# Sensing.net
KiCad netlist of a schematic drawn in Altium Designer
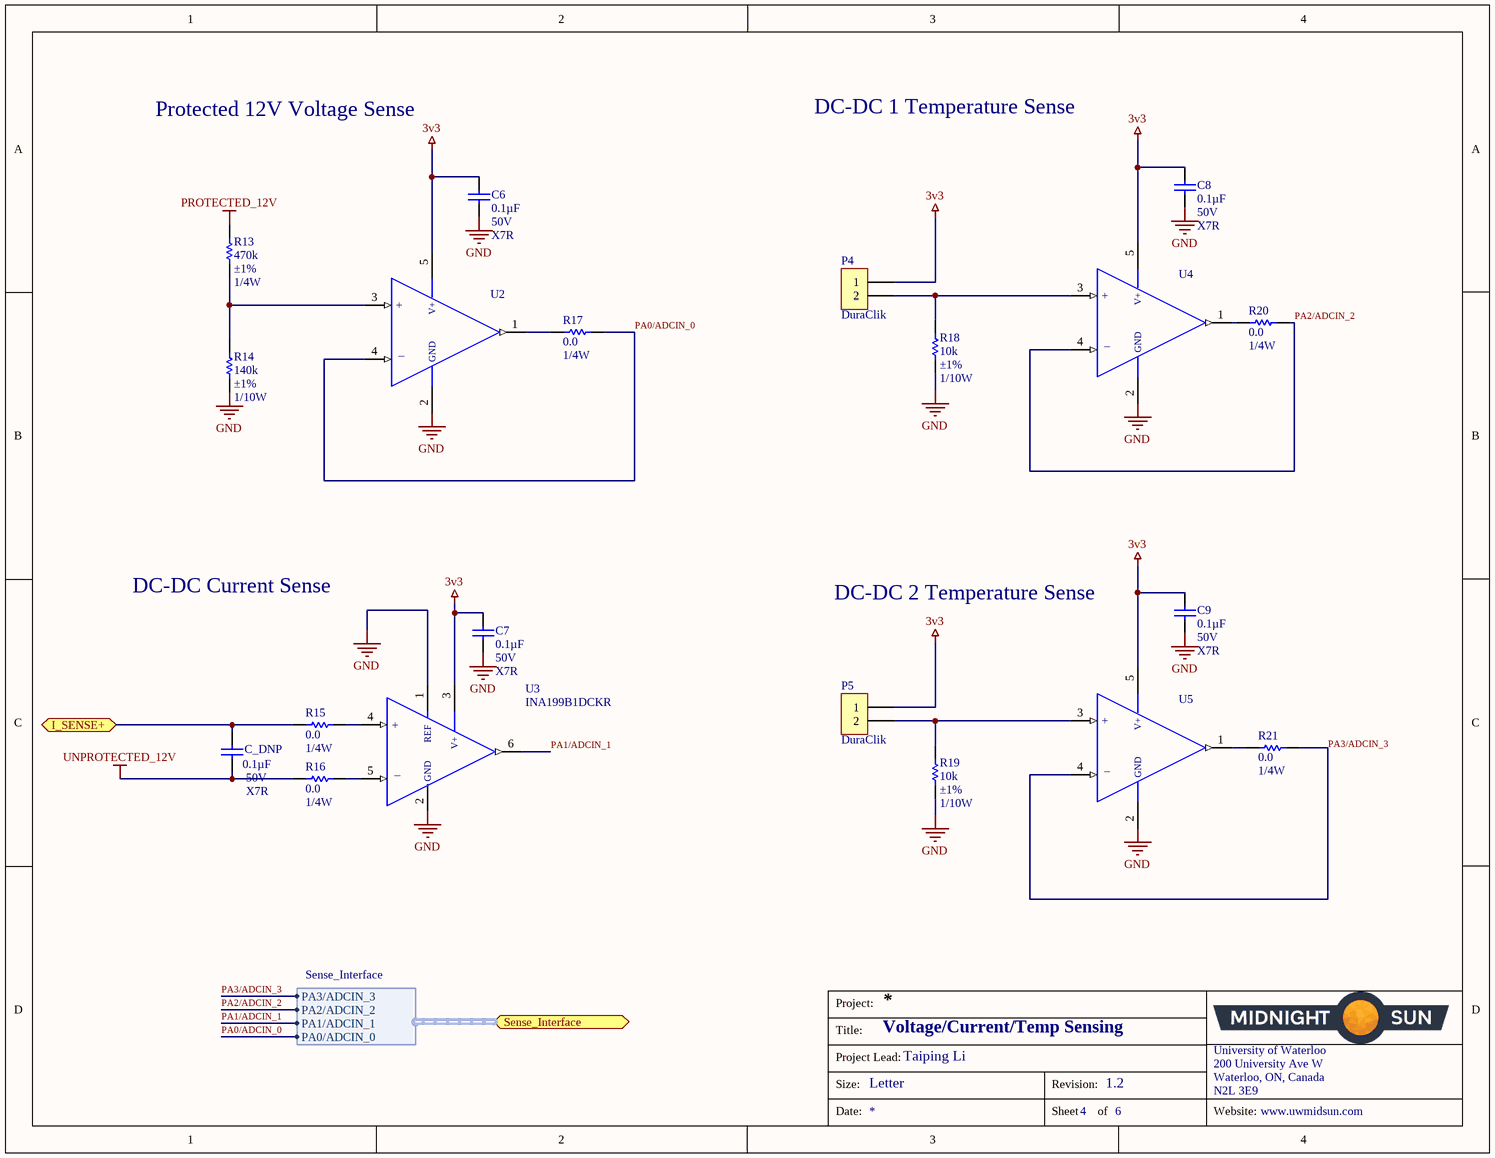
[diagram p0: Sensing.SchDoc]

(export (version "E")
  (design (tool "Eeschema 10.0.6"))
  (components
    (comp (ref "C6")
      (value "CAP CER 0.1UF 50V 10% X7R 0603")
      (footprint "CAP, 0603")
      (description "0.10µF ±10% 50V Ceramic Capacitor X7R 0603 (1608 Metric)")
      (fields
        (field (name "TOLERANCE") "±10%")
        (field (name "CAPACITANCE") "0.1µF")
        (field (name "VOLTAGE") "50V")
        (field (name "TEMPERATURE COEFFICIENT") "X7R")
      )
      (libsource (lib "Schematic Diagrams") (part "CAP CER 0.1UF 50V 10% X7R 0603"))
    )
    (comp (ref "C7")
      (value "CAP CER 0.1UF 50V 10% X7R 0603")
      (footprint "CAP, 0603")
      (description "0.10µF ±10% 50V Ceramic Capacitor X7R 0603 (1608 Metric)")
      (fields
        (field (name "TOLERANCE") "±10%")
        (field (name "CAPACITANCE") "0.1µF")
        (field (name "VOLTAGE") "50V")
        (field (name "TEMPERATURE COEFFICIENT") "X7R")
      )
      (libsource (lib "Schematic Diagrams") (part "CAP CER 0.1UF 50V 10% X7R 0603"))
    )
    (comp (ref "C8")
      (value "CAP CER 0.1UF 50V 10% X7R 0603")
      (footprint "CAP, 0603")
      (description "0.10µF ±10% 50V Ceramic Capacitor X7R 0603 (1608 Metric)")
      (fields
        (field (name "TOLERANCE") "±10%")
        (field (name "CAPACITANCE") "0.1µF")
        (field (name "VOLTAGE") "50V")
        (field (name "TEMPERATURE COEFFICIENT") "X7R")
      )
      (libsource (lib "Schematic Diagrams") (part "CAP CER 0.1UF 50V 10% X7R 0603"))
    )
    (comp (ref "C9")
      (value "CAP CER 0.1UF 50V 10% X7R 0603")
      (footprint "CAP, 0603")
      (description "0.10µF ±10% 50V Ceramic Capacitor X7R 0603 (1608 Metric)")
      (fields
        (field (name "TOLERANCE") "±10%")
        (field (name "CAPACITANCE") "0.1µF")
        (field (name "VOLTAGE") "50V")
        (field (name "TEMPERATURE COEFFICIENT") "X7R")
      )
      (libsource (lib "Schematic Diagrams") (part "CAP CER 0.1UF 50V 10% X7R 0603"))
    )
    (comp (ref "C_DNP")
      (value "CAP CER 0.1UF 50V 10% X7R 0603")
      (footprint "CAP, 0603")
      (description "0.10µF ±10% 50V Ceramic Capacitor X7R 0603 (1608 Metric)")
      (fields
        (field (name "TOLERANCE") "±10%")
        (field (name "CAPACITANCE") "0.1µF")
        (field (name "VOLTAGE") "50V")
        (field (name "TEMPERATURE COEFFICIENT") "X7R")
      )
      (libsource (lib "Schematic Diagrams") (part "CAP CER 0.1UF 50V 10% X7R 0603"))
    )
    (comp (ref "P4")
      (value "CONN 2POS DURA-CLIK 0.079\"")
      (footprint "CONN, 2POS Dura-Click")
      (description "2 Positions Header, Shrouded Connector 0.079\" (2.00mm) Surface Mount, Right Angle Tin")
      (fields (field (name "SERIES") "DuraClik"))
      (libsource (lib "Schematic Diagrams") (part "CONN 2POS DURA-CLIK 0.079{dblquote}"))
    )
    (comp (ref "P5")
      (value "CONN 2POS DURA-CLIK 0.079\"")
      (footprint "CONN, 2POS Dura-Click")
      (description "2 Positions Header, Shrouded Connector 0.079\" (2.00mm) Surface Mount, Right Angle Tin")
      (fields (field (name "SERIES") "DuraClik"))
      (libsource (lib "Schematic Diagrams") (part "CONN 2POS DURA-CLIK 0.079{dblquote}"))
    )
    (comp (ref "R13")
      (value "RES 470K OHM 1% 1/4W 0603")
      (footprint "RES, 0603")
      (description "RES SMD 470K OHM 1% 1/4W 0603")
      (fields
        (field (name "RESISTANCE") "470k")
        (field (name "TOLERANCE") "±1%")
        (field (name "POWER") "1/4W")
      )
      (libsource (lib "Schematic Diagrams") (part "RES 470K OHM 1% 1/4W 0603"))
    )
    (comp (ref "R14")
      (value "RES 140K OHM 1% 1/10W 0603")
      (footprint "RES, 0603")
      (fields
        (field (name "RESISTANCE (OHMS)") "140k")
        (field (name "TOLERANCE") "±1%")
        (field (name "POWER (WATTS)") "1/10W")
      )
      (libsource (lib "Schematic Diagrams") (part "RES 140K OHM 1% 1/10W 0603"))
    )
    (comp (ref "R15")
      (value "RES 0.0 OHM 1/4W 0603")
      (footprint "RES, 0603")
      (description "RES SMD 0.0 OHM JUMPER 1/4W 0603")
      (fields (field (name "RESISTANCE") "0.0") (field (name "POWER (WATTS)") "1/4W"))
      (libsource (lib "Schematic Diagrams") (part "RES 0.0 OHM 1/4W 0603"))
    )
    (comp (ref "R16")
      (value "RES 0.0 OHM 1/4W 0603")
      (footprint "RES, 0603")
      (description "RES SMD 0.0 OHM JUMPER 1/4W 0603")
      (fields (field (name "RESISTANCE") "0.0") (field (name "POWER (WATTS)") "1/4W"))
      (libsource (lib "Schematic Diagrams") (part "RES 0.0 OHM 1/4W 0603"))
    )
    (comp (ref "R17")
      (value "RES 0.0 OHM 1/4W 0603")
      (footprint "RES, 0603")
      (description "RES SMD 0.0 OHM JUMPER 1/4W 0603")
      (fields (field (name "RESISTANCE") "0.0") (field (name "POWER (WATTS)") "1/4W"))
      (libsource (lib "Schematic Diagrams") (part "RES 0.0 OHM 1/4W 0603"))
    )
    (comp (ref "R18")
      (value "RES 10K OHM 1% 1/10W 0603")
      (footprint "RES, 0603")
      (description "RES SMD 10K OHM 1% 1/10W 0603")
      (fields
        (field (name "RESISTANCE") "10k")
        (field (name "TOLERANCE") "±1%")
        (field (name "POWER") "1/10W")
      )
      (libsource (lib "Schematic Diagrams") (part "RES 10K OHM 1% 1/10W 0603"))
    )
    (comp (ref "R19")
      (value "RES 10K OHM 1% 1/10W 0603")
      (footprint "RES, 0603")
      (description "RES SMD 10K OHM 1% 1/10W 0603")
      (fields
        (field (name "RESISTANCE") "10k")
        (field (name "TOLERANCE") "±1%")
        (field (name "POWER") "1/10W")
      )
      (libsource (lib "Schematic Diagrams") (part "RES 10K OHM 1% 1/10W 0603"))
    )
    (comp (ref "R20")
      (value "RES 0.0 OHM 1/4W 0603")
      (footprint "RES, 0603")
      (description "RES SMD 0.0 OHM JUMPER 1/4W 0603")
      (fields (field (name "RESISTANCE") "0.0") (field (name "POWER (WATTS)") "1/4W"))
      (libsource (lib "Schematic Diagrams") (part "RES 0.0 OHM 1/4W 0603"))
    )
    (comp (ref "R21")
      (value "RES 0.0 OHM 1/4W 0603")
      (footprint "RES, 0603")
      (description "RES SMD 0.0 OHM JUMPER 1/4W 0603")
      (fields (field (name "RESISTANCE") "0.0") (field (name "POWER (WATTS)") "1/4W"))
      (libsource (lib "Schematic Diagrams") (part "RES 0.0 OHM 1/4W 0603"))
    )
    (comp (ref "U2")
      (value "IC OP AMP GEN PURPOSE RR 10MHZ SOT-23-5")
      (footprint "IC OP AMP GP RR 10MHZ SOT-23-5")
      (description "General Purpose Amplifier 1 Circuit Rail-to-Rail SOT-23-5")
      (libsource (lib "Schematic Diagrams") (part "IC OP AMP GEN PURPOSE RR 10MHZ SOT-23-5"))
    )
    (comp (ref "U3")
      (value "IC CURRENT AMPLIFIER SC70-6")
      (footprint "IC OP AMP CURR SENSE 80KHZ SC70-6")
      (description "Current Sense Amplifier 1 Circuit SC-70-6")
      (fields (field (name "MANUFACTURER PART NUMBER 1") "INA199B1DCKR"))
      (libsource (lib "Schematic Diagrams") (part "IC CURRENT AMPLIFIER SC70-6"))
    )
    (comp (ref "U4")
      (value "IC OP AMP GEN PURPOSE RR 10MHZ SOT-23-5")
      (footprint "IC OP AMP GP RR 10MHZ SOT-23-5")
      (description "General Purpose Amplifier 1 Circuit Rail-to-Rail SOT-23-5")
      (libsource (lib "Schematic Diagrams") (part "IC OP AMP GEN PURPOSE RR 10MHZ SOT-23-5"))
    )
    (comp (ref "U5")
      (value "IC OP AMP GEN PURPOSE RR 10MHZ SOT-23-5")
      (footprint "IC OP AMP GP RR 10MHZ SOT-23-5")
      (description "General Purpose Amplifier 1 Circuit Rail-to-Rail SOT-23-5")
      (libsource (lib "Schematic Diagrams") (part "IC OP AMP GEN PURPOSE RR 10MHZ SOT-23-5"))
    )
  )
  (nets
    (net (code "2") (name "/I_SENSE+") (class "Default")
      (node (ref "C_DNP") (pin "1") (pinfunction "1_1") (pintype "passive"))
      (node (ref "R15") (pin "1") (pinfunction "1_1") (pintype "passive"))
    )
    (net (code "3") (name "/PA0{slash}ADCIN_0") (class "Default")
      (node (ref "R17") (pin "2") (pinfunction "2_2") (pintype "passive"))
      (node (ref "U2") (pin "4") (pinfunction "-IN_4") (pintype "input"))
    )
    (net (code "4") (name "/PA1{slash}ADCIN_1") (class "Default")
      (node (ref "U3") (pin "6") (pinfunction "OUTPUT_6") (pintype "output"))
    )
    (net (code "5") (name "/PA2{slash}ADCIN_2") (class "Default")
      (node (ref "R20") (pin "2") (pinfunction "2_2") (pintype "passive"))
      (node (ref "U4") (pin "4") (pinfunction "-IN_4") (pintype "input"))
    )
    (net (code "6") (name "/PA3{slash}ADCIN_3") (class "Default")
      (node (ref "R21") (pin "2") (pinfunction "2_2") (pintype "passive"))
      (node (ref "U5") (pin "4") (pinfunction "-IN_4") (pintype "input"))
    )
    (net (code "8") (name "3v3") (class "Default")
      (node (ref "C6") (pin "1") (pinfunction "1_1") (pintype "passive"))
      (node (ref "C7") (pin "1") (pinfunction "1_1") (pintype "passive"))
      (node (ref "C8") (pin "1") (pinfunction "1_1") (pintype "passive"))
      (node (ref "C9") (pin "1") (pinfunction "1_1") (pintype "passive"))
      (node (ref "P4") (pin "1") (pinfunction "1_1") (pintype "passive"))
      (node (ref "P5") (pin "1") (pinfunction "1_1") (pintype "passive"))
      (node (ref "U2") (pin "5") (pinfunction "VDD_5") (pintype "power_in"))
      (node (ref "U3") (pin "3") (pinfunction "V+_3") (pintype "power_in"))
      (node (ref "U4") (pin "5") (pinfunction "VDD_5") (pintype "power_in"))
      (node (ref "U5") (pin "5") (pinfunction "VDD_5") (pintype "power_in"))
    )
    (net (code "9") (name "GND") (class "Default")
      (node (ref "C6") (pin "2") (pinfunction "2_2") (pintype "passive"))
      (node (ref "C7") (pin "2") (pinfunction "2_2") (pintype "passive"))
      (node (ref "C8") (pin "2") (pinfunction "2_2") (pintype "passive"))
      (node (ref "C9") (pin "2") (pinfunction "2_2") (pintype "passive"))
      (node (ref "R14") (pin "2") (pinfunction "2_2") (pintype "passive"))
      (node (ref "R18") (pin "2") (pinfunction "2_2") (pintype "passive"))
      (node (ref "R19") (pin "2") (pinfunction "2_2") (pintype "passive"))
      (node (ref "U2") (pin "2") (pinfunction "VSS_2") (pintype "power_in"))
      (node (ref "U3") (pin "1") (pinfunction "REF_1") (pintype "passive"))
      (node (ref "U3") (pin "2") (pinfunction "GND_2") (pintype "power_in"))
      (node (ref "U4") (pin "2") (pinfunction "VSS_2") (pintype "power_in"))
      (node (ref "U5") (pin "2") (pinfunction "VSS_2") (pintype "power_in"))
    )
    (net (code "10") (name "Net-(U2-+IN)") (class "Default")
      (node (ref "R13") (pin "2") (pinfunction "2_2") (pintype "passive"))
      (node (ref "R14") (pin "1") (pinfunction "1_1") (pintype "passive"))
      (node (ref "U2") (pin "3") (pinfunction "+IN_3") (pintype "input"))
    )
    (net (code "11") (name "Net-(U2-OUTPUT)") (class "Default")
      (node (ref "R17") (pin "1") (pinfunction "1_1") (pintype "passive"))
      (node (ref "U2") (pin "1") (pinfunction "OUTPUT_1") (pintype "output"))
    )
    (net (code "12") (name "Net-(U3-+IN)") (class "Default")
      (node (ref "R15") (pin "2") (pinfunction "2_2") (pintype "passive"))
      (node (ref "U3") (pin "4") (pinfunction "+IN_4") (pintype "input"))
    )
    (net (code "13") (name "Net-(U3--IN)") (class "Default")
      (node (ref "R16") (pin "2") (pinfunction "2_2") (pintype "passive"))
      (node (ref "U3") (pin "5") (pinfunction "-IN_5") (pintype "input"))
    )
    (net (code "14") (name "Net-(U4-+IN)") (class "Default")
      (node (ref "P4") (pin "2") (pinfunction "2_2") (pintype "passive"))
      (node (ref "R18") (pin "1") (pinfunction "1_1") (pintype "passive"))
      (node (ref "U4") (pin "3") (pinfunction "+IN_3") (pintype "input"))
    )
    (net (code "15") (name "Net-(U4-OUTPUT)") (class "Default")
      (node (ref "R20") (pin "1") (pinfunction "1_1") (pintype "passive"))
      (node (ref "U4") (pin "1") (pinfunction "OUTPUT_1") (pintype "output"))
    )
    (net (code "16") (name "Net-(U5-+IN)") (class "Default")
      (node (ref "P5") (pin "2") (pinfunction "2_2") (pintype "passive"))
      (node (ref "R19") (pin "1") (pinfunction "1_1") (pintype "passive"))
      (node (ref "U5") (pin "3") (pinfunction "+IN_3") (pintype "input"))
    )
    (net (code "17") (name "Net-(U5-OUTPUT)") (class "Default")
      (node (ref "R21") (pin "1") (pinfunction "1_1") (pintype "passive"))
      (node (ref "U5") (pin "1") (pinfunction "OUTPUT_1") (pintype "output"))
    )
    (net (code "18") (name "PROTECTED_12V") (class "Default")
      (node (ref "R13") (pin "1") (pinfunction "1_1") (pintype "passive"))
    )
    (net (code "19") (name "UNPROTECTED_12V") (class "Default")
      (node (ref "C_DNP") (pin "2") (pinfunction "2_2") (pintype "passive"))
      (node (ref "R16") (pin "1") (pinfunction "1_1") (pintype "passive"))
    )
  )
)
